# power.net
KiCad netlist of a schematic drawn in EAGLE
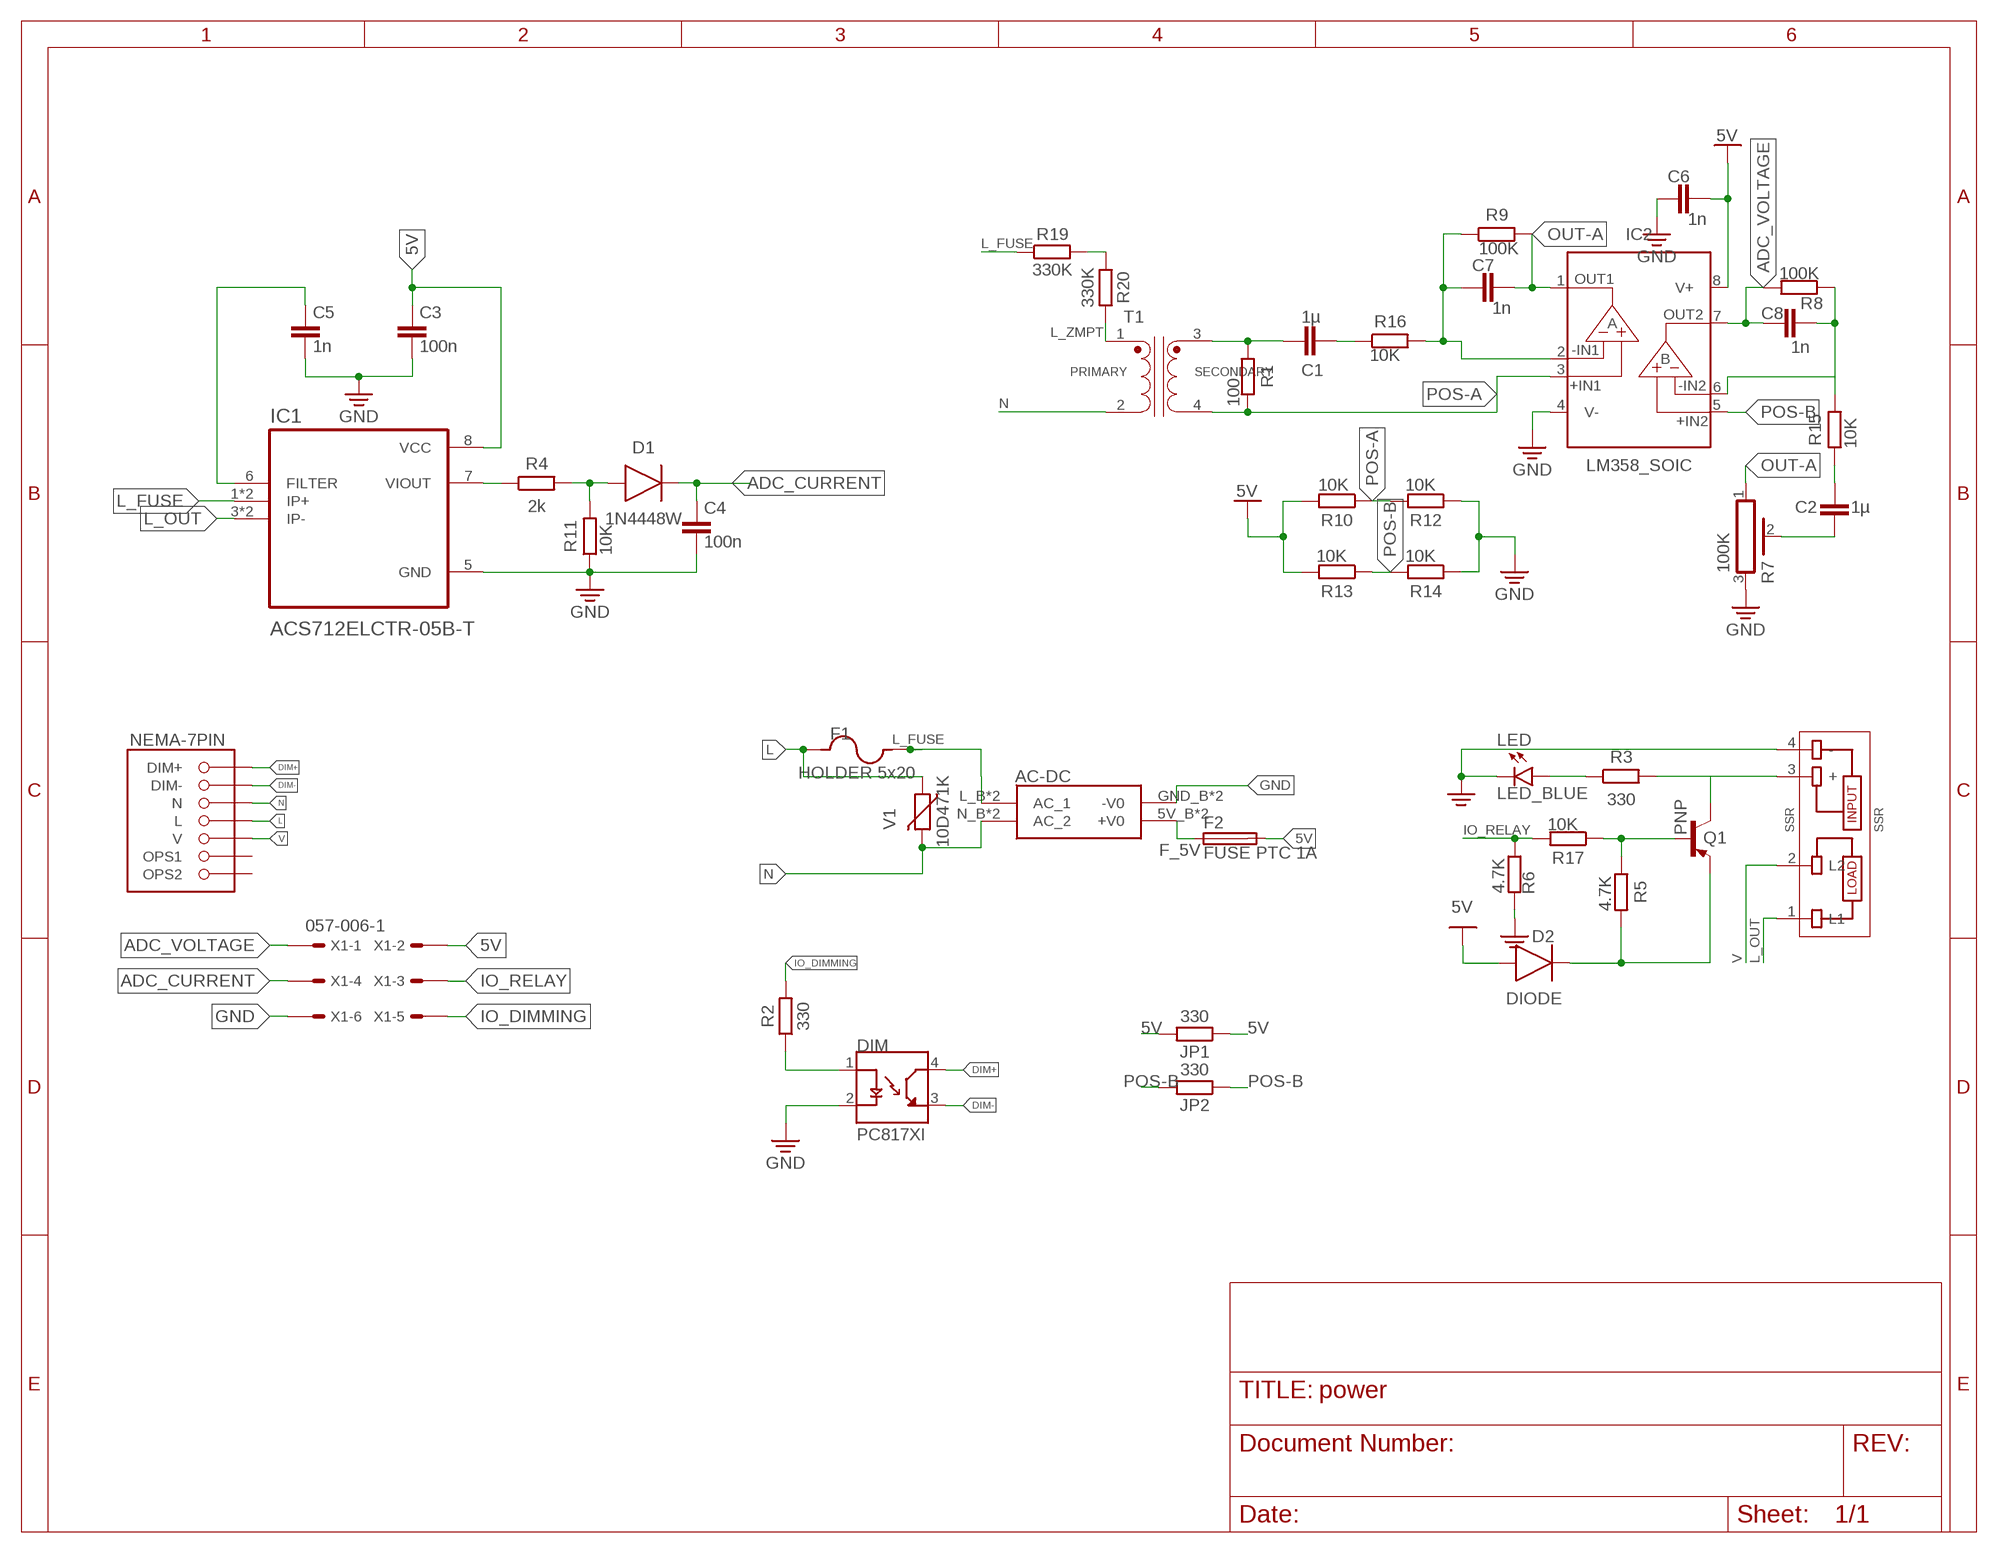
[diagram p0: schematic, sheet 1]

(export (version "E")
  (design (tool "Eeschema 10.0.6"))
  (components
    (comp (ref "AC-DC")
      (value "HI-LINKVERTICAL")
      (footprint "eagle-import:AC-DC_3.5W(VER)")
      (libsource (lib "eagle-import") (part "HI-LINKVERTICAL"))
    )
    (comp (ref "C1")
      (value "1µ")
      (footprint "eagle-import:CAPC2012X110")
      (libsource (lib "eagle-import") (part "CCHIP-0805(2012-METRIC)_"))
    )
    (comp (ref "C2")
      (value "1µ")
      (footprint "eagle-import:CAPC2012X110")
      (libsource (lib "eagle-import") (part "CCHIP-0805(2012-METRIC)_"))
    )
    (comp (ref "C3")
      (value "100n")
      (footprint "eagle-import:CAPC2012X110")
      (libsource (lib "eagle-import") (part "CCHIP-0805(2012-METRIC)_"))
    )
    (comp (ref "C4")
      (value "100n")
      (footprint "eagle-import:CAPC2012X110")
      (libsource (lib "eagle-import") (part "CCHIP-0805(2012-METRIC)_"))
    )
    (comp (ref "C5")
      (value "1n")
      (footprint "eagle-import:CAPC2012X110")
      (libsource (lib "eagle-import") (part "CCHIP-0805(2012-METRIC)_"))
    )
    (comp (ref "C6")
      (value "1n")
      (footprint "eagle-import:CAPC2012X110")
      (libsource (lib "eagle-import") (part "CCHIP-0805(2012-METRIC)_"))
    )
    (comp (ref "C7")
      (value "1n")
      (footprint "eagle-import:CAPC2012X110")
      (libsource (lib "eagle-import") (part "CCHIP-0805(2012-METRIC)_"))
    )
    (comp (ref "C8")
      (value "1n")
      (footprint "eagle-import:CAPC2012X110")
      (libsource (lib "eagle-import") (part "CCHIP-0805(2012-METRIC)_"))
    )
    (comp (ref "D1")
      (value "1N4448W")
      (footprint "eagle-import:SOD3715X135")
      (fields (field (name "MANUFACTURER") "Diodes Incorporated"))
      (libsource (lib "eagle-import") (part "DIODE__SOD123G1N4148W-7-F"))
    )
    (comp (ref "D2")
      (value "DIODE")
      (footprint "eagle-import:DIOM5226X290N")
      (libsource (lib "eagle-import") (part "DIODEDO-214AC(SMA)"))
    )
    (comp (ref "DIM")
      (value "PC817XI")
      (footprint "eagle-import:SOIC254P975X460-4N")
      (fields (field (name "MF") "Sharp"))
      (libsource (lib "eagle-import") (part "PC817XI"))
    )
    (comp (ref "F1")
      (value "HOLDER 5x20")
      (footprint "eagle-import:4527")
      (fields
        (field (name "MANUFACTURER") "Keystone Electronics")
        (field (name "MPN") "4527")
        (field (name "CREATED_BY") "PCBLayout.com")
      )
      (libsource (lib "eagle-import") (part "4527"))
    )
    (comp (ref "F2")
      (value "FUSE PTC 1A")
      (footprint "eagle-import:FUSC3215X82N")
      (libsource (lib "eagle-import") (part "FUSECHIP-1206(3216-METRIC)_"))
    )
    (comp (ref "IC1")
      (value "ACS712ELCTR-05B-T")
      (footprint "eagle-import:SOIC127P600X175-8N@1")
      (libsource (lib "eagle-import") (part "ACS712ELCTR-05B-T"))
    )
    (comp (ref "IC2")
      (value "LM358_SOIC")
      (footprint "eagle-import:SOIC127P600X175-8N")
      (fields (field (name "MANUFACTURER") "Generic"))
      (libsource (lib "eagle-import") (part "LM358_SOIC"))
    )
    (comp (ref "JP1")
      (value "330")
      (footprint "eagle-import:RESC2012X65")
      (libsource (lib "eagle-import") (part "RCHIP-0805(2012-METRIC)_"))
    )
    (comp (ref "JP2")
      (value "330")
      (footprint "eagle-import:RESC2012X65")
      (libsource (lib "eagle-import") (part "RCHIP-0805(2012-METRIC)_"))
    )
    (comp (ref "LED")
      (value "LED_BLUE")
      (footprint "eagle-import:LEDC2012X110N_FLAT-B")
      (libsource (lib "eagle-import") (part "CHIP-FLAT-B_0805"))
    )
    (comp (ref "NEMA-7PIN")
      (value "NEMA-7P")
      (footprint "eagle-import:NEMA-7P")
      (libsource (lib "eagle-import") (part "NEMA-7P"))
    )
    (comp (ref "Q1")
      (value "PNP")
      (footprint "eagle-import:SOT95P237X112-3N")
      (libsource (lib "eagle-import") (part "PNPSOT23-BEC_"))
    )
    (comp (ref "R1")
      (value "100")
      (footprint "eagle-import:RESC2012X65")
      (libsource (lib "eagle-import") (part "RCHIP-0805(2012-METRIC)_"))
    )
    (comp (ref "R2")
      (value "330")
      (footprint "eagle-import:RESC2012X65")
      (libsource (lib "eagle-import") (part "RCHIP-0805(2012-METRIC)_"))
    )
    (comp (ref "R3")
      (value "330")
      (footprint "eagle-import:RESC2012X65")
      (libsource (lib "eagle-import") (part "RCHIP-0805(2012-METRIC)_"))
    )
    (comp (ref "R4")
      (value "2k")
      (footprint "eagle-import:RESC2012X65")
      (libsource (lib "eagle-import") (part "RCHIP-0805(2012-METRIC)_"))
    )
    (comp (ref "R5")
      (value "4.7K")
      (footprint "eagle-import:RESC2012X65")
      (libsource (lib "eagle-import") (part "RCHIP-0805(2012-METRIC)_"))
    )
    (comp (ref "R6")
      (value "4.7K")
      (footprint "eagle-import:RESC2012X65")
      (libsource (lib "eagle-import") (part "RCHIP-0805(2012-METRIC)_"))
    )
    (comp (ref "R7")
      (value "100K")
      (footprint "eagle-import:PV36W")
      (fields (field (name "MANUFACTURER") "BOURNS") (field (name "MPN") "PV36W"))
      (libsource (lib "eagle-import") (part "PV36W"))
    )
    (comp (ref "R8")
      (value "100K")
      (footprint "eagle-import:RESC2012X65")
      (libsource (lib "eagle-import") (part "RCHIP-0805(2012-METRIC)_"))
    )
    (comp (ref "R9")
      (value "100K")
      (footprint "eagle-import:RESC2012X65")
      (libsource (lib "eagle-import") (part "RCHIP-0805(2012-METRIC)_"))
    )
    (comp (ref "R10")
      (value "10K")
      (footprint "eagle-import:RESC2012X65")
      (libsource (lib "eagle-import") (part "RCHIP-0805(2012-METRIC)_"))
    )
    (comp (ref "R11")
      (value "10K")
      (footprint "eagle-import:RESC2012X65")
      (libsource (lib "eagle-import") (part "RCHIP-0805(2012-METRIC)_"))
    )
    (comp (ref "R12")
      (value "10K")
      (footprint "eagle-import:RESC2012X65")
      (libsource (lib "eagle-import") (part "RCHIP-0805(2012-METRIC)_"))
    )
    (comp (ref "R13")
      (value "10K")
      (footprint "eagle-import:RESC2012X65")
      (libsource (lib "eagle-import") (part "RCHIP-0805(2012-METRIC)_"))
    )
    (comp (ref "R14")
      (value "10K")
      (footprint "eagle-import:RESC2012X65")
      (libsource (lib "eagle-import") (part "RCHIP-0805(2012-METRIC)_"))
    )
    (comp (ref "R15")
      (value "10K")
      (footprint "eagle-import:RESC2012X65")
      (libsource (lib "eagle-import") (part "RCHIP-0805(2012-METRIC)_"))
    )
    (comp (ref "R16")
      (value "10K")
      (footprint "eagle-import:RESC2012X65")
      (libsource (lib "eagle-import") (part "RCHIP-0805(2012-METRIC)_"))
    )
    (comp (ref "R17")
      (value "10K")
      (footprint "eagle-import:RESC2012X65")
      (libsource (lib "eagle-import") (part "RCHIP-0805(2012-METRIC)_"))
    )
    (comp (ref "R19")
      (value "330K")
      (footprint "eagle-import:RESAD724W46L381D178B")
      (libsource (lib "eagle-import") (part "RAXIAL-7.2MM-PITCH_"))
    )
    (comp (ref "R20")
      (value "330K")
      (footprint "eagle-import:RESAD724W46L381D178B")
      (libsource (lib "eagle-import") (part "RAXIAL-7.2MM-PITCH_"))
    )
    (comp (ref "SSR")
      (value "SSR")
      (footprint "eagle-import:SSR_G3MB-202P")
      (fields (field (name "MANUFACTURER") "Omron"))
      (libsource (lib "eagle-import") (part "SSR"))
    )
    (comp (ref "T1")
      (value "ZMPT101B")
      (footprint "eagle-import:ZMPT101B")
      (fields (field (name "MANUFACTURER") "Qingxian Zeming Langxi Electronic"))
      (libsource (lib "eagle-import") (part "ZMPT101B"))
    )
    (comp (ref "V1")
      (value "10D471K")
      (footprint "eagle-import:MOV-10D561")
      (libsource (lib "eagle-import") (part "VARISTOR"))
    )
    (comp (ref "X1")
      (value "057-006-1")
      (footprint "eagle-import:057-006-1")
      (libsource (lib "eagle-import") (part "057-006-1"))
    )
  )
  (nets
    (net (code "1") (name "/F_5V") (class "Default")
      (node (ref "AC-DC") (pin "5V_B") (pinfunction "+V0_5V_B") (pintype "bidirectional"))
      (node (ref "AC-DC") (pin "5V_T") (pinfunction "+V0_5V_T") (pintype "bidirectional"))
      (node (ref "F2") (pin "1") (pinfunction "1_1") (pintype "passive"))
    )
    (net (code "2") (name "/L_ZMPT") (class "Default")
      (node (ref "R20") (pin "2") (pinfunction "2_2") (pintype "passive"))
      (node (ref "T1") (pin "1") (pinfunction "1_1") (pintype "passive"))
    )
    (net (code "3") (name "5V") (class "Default")
      (node (ref "C3") (pin "1") (pinfunction "1_1") (pintype "passive"))
      (node (ref "C6") (pin "2") (pinfunction "2_2") (pintype "passive"))
      (node (ref "D2") (pin "2") (pinfunction "A_2") (pintype "passive"))
      (node (ref "F2") (pin "2") (pinfunction "2_2") (pintype "passive"))
      (node (ref "IC1") (pin "8") (pinfunction "VCC_8") (pintype "power_in"))
      (node (ref "IC2") (pin "8") (pinfunction "V+_8") (pintype "bidirectional"))
      (node (ref "JP1") (pin "1") (pinfunction "1_1") (pintype "passive"))
      (node (ref "JP1") (pin "2") (pinfunction "2_2") (pintype "passive"))
      (node (ref "R10") (pin "2") (pinfunction "2_2") (pintype "passive"))
      (node (ref "R13") (pin "2") (pinfunction "2_2") (pintype "passive"))
      (node (ref "X1") (pin "2") (pinfunction "S_2") (pintype "passive"))
    )
    (net (code "4") (name "ADC_CURRENT") (class "Default")
      (node (ref "C4") (pin "1") (pinfunction "1_1") (pintype "passive"))
      (node (ref "D1") (pin "1") (pinfunction "C_1") (pintype "passive"))
      (node (ref "X1") (pin "4") (pinfunction "S_4") (pintype "passive"))
    )
    (net (code "5") (name "ADC_VOLTAGE") (class "Default")
      (node (ref "C8") (pin "1") (pinfunction "1_1") (pintype "passive"))
      (node (ref "IC2") (pin "7") (pinfunction "OUT2_7") (pintype "passive"))
      (node (ref "R8") (pin "2") (pinfunction "2_2") (pintype "passive"))
      (node (ref "X1") (pin "1") (pinfunction "S_1") (pintype "passive"))
    )
    (net (code "6") (name "DIM+") (class "Default")
      (node (ref "DIM") (pin "4") (pinfunction "CT_4") (pintype "passive"))
      (node (ref "NEMA-7PIN") (pin "DIM+") (pinfunction "DIM+_DIM+") (pintype "output"))
    )
    (net (code "7") (name "DIM-") (class "Default")
      (node (ref "DIM") (pin "3") (pinfunction "ET_3") (pintype "passive"))
      (node (ref "NEMA-7PIN") (pin "DIM-") (pinfunction "DIM-_DIM-") (pintype "output"))
    )
    (net (code "8") (name "GND") (class "Default")
      (node (ref "AC-DC") (pin "GND_B") (pinfunction "-V0_GND_B") (pintype "bidirectional"))
      (node (ref "AC-DC") (pin "GND_T") (pinfunction "-V0_GND_T") (pintype "bidirectional"))
      (node (ref "C3") (pin "2") (pinfunction "2_2") (pintype "passive"))
      (node (ref "C4") (pin "2") (pinfunction "2_2") (pintype "passive"))
      (node (ref "C5") (pin "2") (pinfunction "2_2") (pintype "passive"))
      (node (ref "C6") (pin "1") (pinfunction "1_1") (pintype "passive"))
      (node (ref "DIM") (pin "2") (pinfunction "C_2") (pintype "passive"))
      (node (ref "IC1") (pin "5") (pinfunction "GND_5") (pintype "power_in"))
      (node (ref "IC2") (pin "4") (pinfunction "V-_4") (pintype "bidirectional"))
      (node (ref "LED") (pin "C") (pinfunction "C_C") (pintype "passive"))
      (node (ref "R11") (pin "1") (pinfunction "1_1") (pintype "passive"))
      (node (ref "R12") (pin "1") (pinfunction "1_1") (pintype "passive"))
      (node (ref "R14") (pin "1") (pinfunction "1_1") (pintype "passive"))
      (node (ref "R6") (pin "2") (pinfunction "2_2") (pintype "passive"))
      (node (ref "R7") (pin "3") (pinfunction "P$3_3") (pintype "passive"))
      (node (ref "SSR") (pin "4") (pinfunction "-_4") (pintype "power_in"))
      (node (ref "X1") (pin "6") (pinfunction "S_6") (pintype "passive"))
    )
    (net (code "9") (name "IO_DIMMING") (class "Default")
      (node (ref "R2") (pin "2") (pinfunction "2_2") (pintype "passive"))
      (node (ref "X1") (pin "5") (pinfunction "S_5") (pintype "passive"))
    )
    (net (code "10") (name "IO_RELAY") (class "Default")
      (node (ref "R17") (pin "2") (pinfunction "2_2") (pintype "passive"))
      (node (ref "R6") (pin "1") (pinfunction "1_1") (pintype "passive"))
      (node (ref "X1") (pin "3") (pinfunction "S_3") (pintype "passive"))
    )
    (net (code "11") (name "L") (class "Default")
      (node (ref "F1") (pin "1") (pinfunction "1_1") (pintype "passive"))
      (node (ref "NEMA-7PIN") (pin "L") (pinfunction "L_L") (pintype "output"))
      (node (ref "V1") (pin "1") (pinfunction "1_1") (pintype "passive"))
    )
    (net (code "12") (name "L_FUSE") (class "Default")
      (node (ref "AC-DC") (pin "L_B") (pinfunction "AC_1_L_B") (pintype "bidirectional"))
      (node (ref "AC-DC") (pin "L_T") (pinfunction "AC_1_L_T") (pintype "bidirectional"))
      (node (ref "F1") (pin "2") (pinfunction "2_2") (pintype "passive"))
      (node (ref "IC1") (pin "1") (pinfunction "IP+_1") (pintype "input"))
      (node (ref "IC1") (pin "2") (pinfunction "IP+_2") (pintype "input"))
      (node (ref "R19") (pin "1") (pinfunction "1_1") (pintype "passive"))
    )
    (net (code "13") (name "L_OUT") (class "Default")
      (node (ref "IC1") (pin "3") (pinfunction "IP-_3") (pintype "input"))
      (node (ref "IC1") (pin "4") (pinfunction "IP-_4") (pintype "input"))
      (node (ref "SSR") (pin "1") (pinfunction "L1_1") (pintype "power_in"))
    )
    (net (code "14") (name "N") (class "Default")
      (node (ref "AC-DC") (pin "N_B") (pinfunction "AC_2_N_B") (pintype "bidirectional"))
      (node (ref "AC-DC") (pin "N_T") (pinfunction "AC_2_N_T") (pintype "bidirectional"))
      (node (ref "NEMA-7PIN") (pin "N") (pinfunction "N_N") (pintype "output"))
      (node (ref "T1") (pin "2") (pinfunction "2_2") (pintype "passive"))
      (node (ref "V1") (pin "2") (pinfunction "2_2") (pintype "passive"))
    )
    (net (code "15") (name "Net-(C1-Pad1)") (class "Default")
      (node (ref "C1") (pin "1") (pinfunction "1_1") (pintype "passive"))
      (node (ref "R1") (pin "1") (pinfunction "1_1") (pintype "passive"))
      (node (ref "T1") (pin "3") (pinfunction "3_3") (pintype "passive"))
    )
    (net (code "16") (name "Net-(C1-Pad2)") (class "Default")
      (node (ref "C1") (pin "2") (pinfunction "2_2") (pintype "passive"))
      (node (ref "R16") (pin "1") (pinfunction "1_1") (pintype "passive"))
    )
    (net (code "17") (name "Net-(C2-Pad2)") (class "Default")
      (node (ref "C2") (pin "2") (pinfunction "2_2") (pintype "passive"))
      (node (ref "R15") (pin "1") (pinfunction "1_1") (pintype "passive"))
    )
    (net (code "18") (name "Net-(D1-A)") (class "Default")
      (node (ref "D1") (pin "2") (pinfunction "A_2") (pintype "passive"))
      (node (ref "R11") (pin "2") (pinfunction "2_2") (pintype "passive"))
      (node (ref "R4") (pin "2") (pinfunction "2_2") (pintype "passive"))
    )
    (net (code "19") (name "Net-(D2-C)") (class "Default")
      (node (ref "D2") (pin "1") (pinfunction "C_1") (pintype "passive"))
      (node (ref "Q1") (pin "2") (pinfunction "E_2") (pintype "passive"))
      (node (ref "R5") (pin "2") (pinfunction "2_2") (pintype "passive"))
    )
    (net (code "20") (name "Net-(DIM-A)") (class "Default")
      (node (ref "DIM") (pin "1") (pinfunction "A_1") (pintype "passive"))
      (node (ref "R2") (pin "1") (pinfunction "1_1") (pintype "passive"))
    )
    (net (code "21") (name "Net-(IC1-FILTER)") (class "Default")
      (node (ref "C5") (pin "1") (pinfunction "1_1") (pintype "passive"))
      (node (ref "IC1") (pin "6") (pinfunction "FILTER_6") (pintype "input"))
    )
    (net (code "22") (name "Net-(IC1-VIOUT)") (class "Default")
      (node (ref "IC1") (pin "7") (pinfunction "VIOUT_7") (pintype "output"))
      (node (ref "R4") (pin "1") (pinfunction "1_1") (pintype "passive"))
    )
    (net (code "23") (name "Net-(IC2--IN1)") (class "Default")
      (node (ref "C7") (pin "1") (pinfunction "1_1") (pintype "passive"))
      (node (ref "IC2") (pin "2") (pinfunction "-IN1_2") (pintype "input"))
      (node (ref "R16") (pin "2") (pinfunction "2_2") (pintype "passive"))
      (node (ref "R9") (pin "1") (pinfunction "1_1") (pintype "passive"))
    )
    (net (code "24") (name "Net-(IC2--IN2)") (class "Default")
      (node (ref "C8") (pin "2") (pinfunction "2_2") (pintype "passive"))
      (node (ref "IC2") (pin "6") (pinfunction "-IN2_6") (pintype "passive"))
      (node (ref "R15") (pin "2") (pinfunction "2_2") (pintype "passive"))
      (node (ref "R8") (pin "1") (pinfunction "1_1") (pintype "passive"))
    )
    (net (code "25") (name "Net-(LED-PadA)") (class "Default")
      (node (ref "LED") (pin "A") (pinfunction "A_A") (pintype "passive"))
      (node (ref "R3") (pin "1") (pinfunction "1_1") (pintype "passive"))
    )
    (net (code "26") (name "Net-(Q1-B)") (class "Default")
      (node (ref "Q1") (pin "1") (pinfunction "B_1") (pintype "passive"))
      (node (ref "R17") (pin "1") (pinfunction "1_1") (pintype "passive"))
      (node (ref "R5") (pin "1") (pinfunction "1_1") (pintype "passive"))
    )
    (net (code "27") (name "Net-(Q1-C)") (class "Default")
      (node (ref "Q1") (pin "3") (pinfunction "C_3") (pintype "passive"))
      (node (ref "R3") (pin "2") (pinfunction "2_2") (pintype "passive"))
      (node (ref "SSR") (pin "3") (pinfunction "+_3") (pintype "power_in"))
    )
    (net (code "28") (name "Net-(R7-P$2)") (class "Default")
      (node (ref "C2") (pin "1") (pinfunction "1_1") (pintype "passive"))
      (node (ref "R7") (pin "2") (pinfunction "P$2_2") (pintype "passive"))
    )
    (net (code "29") (name "Net-(R19-Pad2)") (class "Default")
      (node (ref "R19") (pin "2") (pinfunction "2_2") (pintype "passive"))
      (node (ref "R20") (pin "1") (pinfunction "1_1") (pintype "passive"))
    )
    (net (code "30") (name "OUT-A") (class "Default")
      (node (ref "C7") (pin "2") (pinfunction "2_2") (pintype "passive"))
      (node (ref "IC2") (pin "1") (pinfunction "OUT1_1") (pintype "passive"))
      (node (ref "R7") (pin "1") (pinfunction "P$1_1") (pintype "passive"))
      (node (ref "R9") (pin "2") (pinfunction "2_2") (pintype "passive"))
    )
    (net (code "31") (name "POS-A") (class "Default")
      (node (ref "IC2") (pin "3") (pinfunction "+IN1_3") (pintype "input"))
      (node (ref "R1") (pin "2") (pinfunction "2_2") (pintype "passive"))
      (node (ref "R10") (pin "1") (pinfunction "1_1") (pintype "passive"))
      (node (ref "R12") (pin "2") (pinfunction "2_2") (pintype "passive"))
      (node (ref "T1") (pin "4") (pinfunction "4_4") (pintype "passive"))
    )
    (net (code "32") (name "POS-B") (class "Default")
      (node (ref "IC2") (pin "5") (pinfunction "+IN2_5") (pintype "passive"))
      (node (ref "JP2") (pin "1") (pinfunction "1_1") (pintype "passive"))
      (node (ref "JP2") (pin "2") (pinfunction "2_2") (pintype "passive"))
      (node (ref "R13") (pin "1") (pinfunction "1_1") (pintype "passive"))
      (node (ref "R14") (pin "2") (pinfunction "2_2") (pintype "passive"))
    )
    (net (code "33") (name "V") (class "Default")
      (node (ref "NEMA-7PIN") (pin "V") (pinfunction "V_V") (pintype "output"))
      (node (ref "SSR") (pin "2") (pinfunction "L2_2") (pintype "power_in"))
    )
    (net (code "34") (name "unconnected-(NEMA-7PIN-PadOPS1)") (class "Default")
      (node (ref "NEMA-7PIN") (pin "OPS1") (pinfunction "OPS1_OPS1") (pintype "output"))
    )
    (net (code "35") (name "unconnected-(NEMA-7PIN-PadOPS2)") (class "Default")
      (node (ref "NEMA-7PIN") (pin "OPS2") (pinfunction "OPS2_OPS2") (pintype "output"))
    )
  )
)
